# NodeMCU1_0.net
KiCad netlist of a schematic drawn in Altium Designer
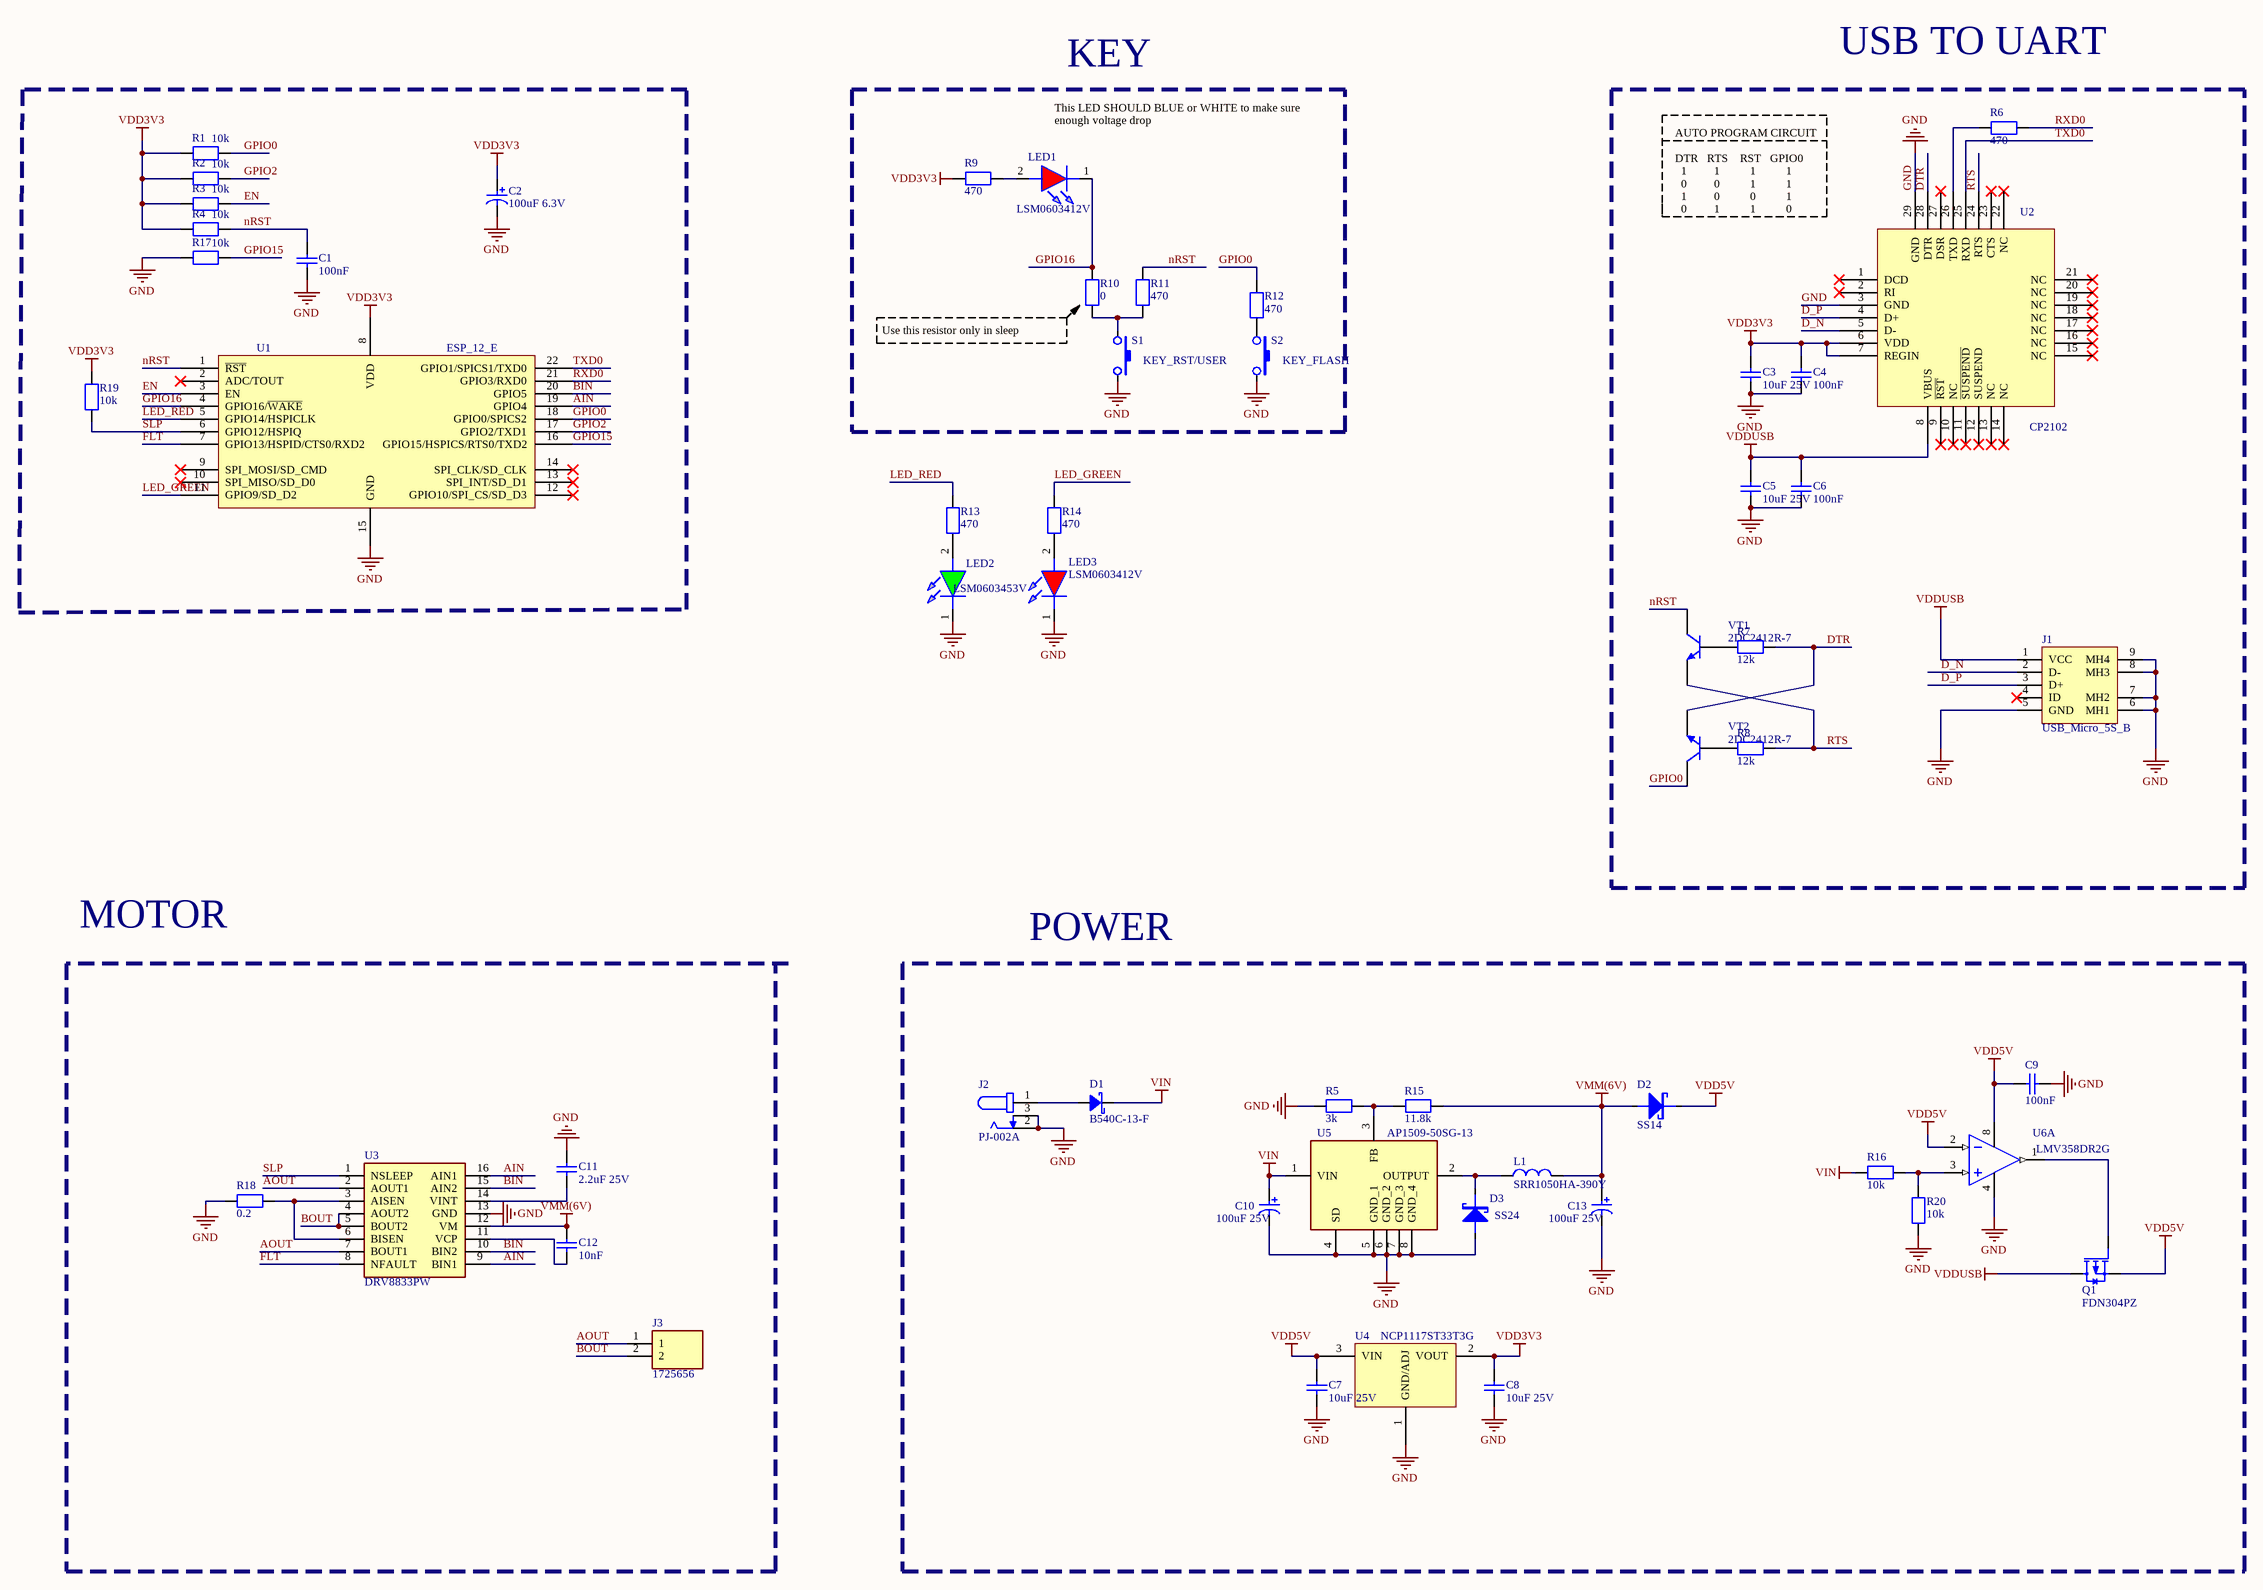
[diagram p0: NodeMCU1.0.SchDoc]

(export (version "E")
  (design (tool "Eeschema 10.0.6"))
  (components
    (comp (ref "C1")
      (value "100nF")
      (footprint "SMT_C_0603")
      (description "Multilayer Ceramic Capacitors MLCC - SMD/SMT 50V 100nF X7R 0603 10%")
      (fields
        (field (name "MANUFACTURER") "Yageo")
        (field (name "MANUFACTURER PART NUMBER") "CS0603KRX7R9BB104")
      )
      (libsource (lib "NodeMCU1.0") (part "SMT CAP 100nF 50V(0603)"))
    )
    (comp (ref "C2")
      (value "100uF 6.3V")
      (footprint "SMT_C_Tantalum_B")
      (description "Tantalum Capacitors - Solid SMD 6.3V 100uF 1210 ESR=1.7Ohms 20%")
      (fields
        (field (name "MANUFACTURER PART NUMBER") "TAJB107M006RNJ")
        (field (name "MANUFACTURER") "KYOCERA AVX")
      )
      (libsource (lib "NodeMCU1.0") (part "SMT ECAP 100uF(SMT_C)"))
    )
    (comp (ref "C3")
      (value "10uF 25V")
      (footprint "SMT_C_0603")
      (description "Multilayer Ceramic Capacitors MLCC - SMD/SMT 25 V 10 uF X5R 0603 20%")
      (fields
        (field (name "MANUFACTURER PART NUMBER") "CC0603MRX5R8BB106")
        (field (name "MANUFACTURER") "YAGEO")
      )
      (libsource (lib "NodeMCU1.0") (part "SMT CAP 10uF 25V(0603)"))
    )
    (comp (ref "C4")
      (value "100nF")
      (footprint "SMT_C_0603")
      (description "Multilayer Ceramic Capacitors MLCC - SMD/SMT 50V 100nF X7R 0603 10%")
      (fields
        (field (name "MANUFACTURER") "Yageo")
        (field (name "MANUFACTURER PART NUMBER") "CS0603KRX7R9BB104")
      )
      (libsource (lib "NodeMCU1.0") (part "SMT CAP 100nF 50V(0603)"))
    )
    (comp (ref "C5")
      (value "10uF 25V")
      (footprint "SMT_C_0603")
      (description "Multilayer Ceramic Capacitors MLCC - SMD/SMT 25 V 10 uF X5R 0603 20%")
      (fields
        (field (name "MANUFACTURER PART NUMBER") "CC0603MRX5R8BB106")
        (field (name "MANUFACTURER") "YAGEO")
      )
      (libsource (lib "NodeMCU1.0") (part "SMT CAP 10uF 25V(0603)"))
    )
    (comp (ref "C6")
      (value "100nF")
      (footprint "SMT_C_0603")
      (description "Multilayer Ceramic Capacitors MLCC - SMD/SMT 50V 100nF X7R 0603 10%")
      (fields
        (field (name "MANUFACTURER") "Yageo")
        (field (name "MANUFACTURER PART NUMBER") "CS0603KRX7R9BB104")
      )
      (libsource (lib "NodeMCU1.0") (part "SMT CAP 100nF 50V(0603)"))
    )
    (comp (ref "C7")
      (value "10uF 25V")
      (footprint "SMT_C_0805")
      (description "Multilayer Ceramic Capacitors MLCC - SMD/SMT 25 V 10 uF X6S 0805 10%")
      (fields
        (field (name "MANUFACTURER PART NUMBER") "CC0805KKX6S8BB106")
        (field (name "MANUFACTURER") "YAGEO")
      )
      (libsource (lib "NodeMCU1.0") (part "SMT CAP 10uF 25V(0805)"))
    )
    (comp (ref "C8")
      (value "10uF 25V")
      (footprint "SMT_C_0603")
      (description "Multilayer Ceramic Capacitors MLCC - SMD/SMT 25 V 10 uF X5R 0603 20%")
      (fields
        (field (name "MANUFACTURER PART NUMBER") "CC0603MRX5R8BB106")
        (field (name "MANUFACTURER") "YAGEO")
      )
      (libsource (lib "NodeMCU1.0") (part "SMT CAP 10uF 25V(0603)"))
    )
    (comp (ref "C9")
      (value "100nF")
      (footprint "SMT_C_0603")
      (description "Multilayer Ceramic Capacitors MLCC - SMD/SMT 50V 100nF X7R 0603 10%")
      (fields
        (field (name "MANUFACTURER") "Yageo")
        (field (name "MANUFACTURER PART NUMBER") "CS0603KRX7R9BB104")
      )
      (libsource (lib "NodeMCU1.0") (part "SMT CAP 100nF 50V(0603)"))
    )
    (comp (ref "C10")
      (value "100uF 25V")
      (footprint "CAPPRD250W50D630H1250")
      (description "Aluminium Electrolytic Capacitors - Radial Leaded 25V 100uF 85C 2k Hour Radial")
      (fields
        (field (name "MANUFACTURER") "Kemet")
        (field (name "MANUFACTURER PART NUMBER") "ESK107M025AE3AA")
      )
      (libsource (lib "NodeMCU1.0") (part "ECAP 100uF 25V"))
    )
    (comp (ref "C11")
      (value "2.2uF 25V")
      (footprint "SMT_C_0603")
      (description "Multilayer Ceramic Capacitors MLCC - SMD/SMT 25 V 2.2 uF X5R 0603 20%")
      (fields
        (field (name "MANUFACTURER PART NUMBER") "CC0603MRX5R8BB225")
        (field (name "MANUFACTURER") "YAGEO")
      )
      (libsource (lib "NodeMCU1.0") (part "SMT CAP 2.2uF 25V(0603)"))
    )
    (comp (ref "C12")
      (value "10nF")
      (footprint "SMT_C_0603")
      (description "Multilayer Ceramic Capacitors MLCC - SMD/SMT 50V 10nF X7R 0603 10%")
      (fields
        (field (name "MANUFACTURER") "Yageo")
        (field (name "MANUFACTURER PART NUMBER") "CS0603KRX7R9BB103")
      )
      (libsource (lib "NodeMCU1.0") (part "SMT CAP 10nF 50V(0603)"))
    )
    (comp (ref "C13")
      (value "100uF 25V")
      (footprint "CAPPRD250W50D630H1250")
      (description "Aluminium Electrolytic Capacitors - Radial Leaded 25V 100uF 85C 2k Hour Radial")
      (fields
        (field (name "MANUFACTURER") "Kemet")
        (field (name "MANUFACTURER PART NUMBER") "ESK107M025AE3AA")
      )
      (libsource (lib "NodeMCU1.0") (part "ECAP 100uF 25V"))
    )
    (comp (ref "D1")
      (value "B540C-13-F")
      (footprint "B540C-13-F")
      (description "DIODE SCHOTTKY 40V 5A SMC")
      (fields (field (name "MANUFACTURER") "Diodes"))
      (libsource (lib "NodeMCU1.0") (part "DIODE 10TQ035"))
    )
    (comp (ref "D2")
      (value "SS14")
      (footprint "SS14")
      (description "Schottky Diodes & Rectifiers SMA 40V 1.0A")
      (fields (field (name "MANUFACTURER") "onsemi / Fairchild"))
      (libsource (lib "NodeMCU1.0") (part "SS14"))
    )
    (comp (ref "D3")
      (value "SS24")
      (footprint "DIOM5436X247N")
      (description "Schottky Diodes & Rectifiers 2A, 40V, Schottky Rectifier")
      (fields (field (name "MANUFACTURER") "Taiwan Semiconductor"))
      (libsource (lib "NodeMCU1.0") (part "SS24"))
    )
    (comp (ref "J1")
      (value "USB_Micro_5S_B")
      (footprint "USB_MICRO_5S_B")
      (description "USB micro female SMT with 4 fixed foot")
      (fields
        (field (name "MANUFACTURER PART NUMBER") "614105150721")
        (field (name "MANUFACTURER") "Wurth Electronics")
      )
      (libsource (lib "NodeMCU1.0") (part "USB_Micro_5S_B"))
    )
    (comp (ref "J2")
      (value "PJ-002A")
      (footprint "PJ002A")
      (description "CONN PWR JACK 2X5.5MM SOLDER")
      (fields (field (name "MANUFACTURER") "CUI Devices"))
      (libsource (lib "NodeMCU1.0") (part "PJ-002A"))
    )
    (comp (ref "J3")
      (value "1725656")
      (footprint "1725656")
      (fields (field (name "MANUFACTURER") "Phoenix Contact"))
      (libsource (lib "NodeMCU1.0") (part "1725656"))
    )
    (comp (ref "L1")
      (value "SRR1050HA-390Y")
      (footprint "INDPM102100X510N")
      (description "Ind,10x10.2x4.8mm,39uH+/-30%,2.25A,shd")
      (fields (field (name "MANUFACTURER") "Bourns"))
      (libsource (lib "NodeMCU1.0") (part "INDUCTOR 39uH 2.25A"))
    )
    (comp (ref "LED1")
      (value "LSM0603412V")
      (footprint "LSM0603412V")
      (description "Standard LEDs - SMD SMD 0603 2V 100mcd RED")
      (fields (field (name "MANUFACTURER") "Visual Communications Company"))
      (libsource (lib "NodeMCU1.0") (part "LSM0603412V"))
    )
    (comp (ref "LED2")
      (value "LSM0603453V")
      (footprint "LEDC1608X55N")
      (description "Standard LEDs - SMD SMD 0603 3V 1000mcd GREEN")
      (fields (field (name "MANUFACTURER") "Visual Communications Company"))
      (libsource (lib "NodeMCU1.0") (part "LSM0603453V"))
    )
    (comp (ref "LED3")
      (value "LSM0603412V")
      (footprint "LSM0603412V")
      (description "Standard LEDs - SMD SMD 0603 2V 100mcd RED")
      (fields (field (name "MANUFACTURER") "Visual Communications Company"))
      (libsource (lib "NodeMCU1.0") (part "LSM0603412V"))
    )
    (comp (ref "Q1")
      (value "FDN304PZ")
      (footprint "SOT95P251X112-3N")
      (description "P-Channel MOSFET")
      (fields (field (name "MANUFACTURER") "onsemi / Fairchild"))
      (libsource (lib "NodeMCU1.0") (part "MOSFET-P"))
    )
    (comp (ref "R1")
      (value "10k")
      (footprint "SMT_R_0603")
      (description "Thick Film Resistors - SMD 10 kOhms 100mW 0603 1%")
      (fields
        (field (name "MANUFACTURER") "Yageo")
        (field (name "MANUFACTURER PART NUMBER") "RC0603FR-0710KL")
      )
      (libsource (lib "NodeMCU1.0") (part "RES 10K 0.1W 1%"))
    )
    (comp (ref "R2")
      (value "10k")
      (footprint "SMT_R_0603")
      (description "Thick Film Resistors - SMD 10 kOhms 100mW 0603 1%")
      (fields
        (field (name "MANUFACTURER") "Yageo")
        (field (name "MANUFACTURER PART NUMBER") "RC0603FR-0710KL")
      )
      (libsource (lib "NodeMCU1.0") (part "RES 10K 0.1W 1%"))
    )
    (comp (ref "R3")
      (value "10k")
      (footprint "SMT_R_0603")
      (description "Thick Film Resistors - SMD 10 kOhms 100mW 0603 1%")
      (fields
        (field (name "MANUFACTURER") "Yageo")
        (field (name "MANUFACTURER PART NUMBER") "RC0603FR-0710KL")
      )
      (libsource (lib "NodeMCU1.0") (part "RES 10K 0.1W 1%"))
    )
    (comp (ref "R4")
      (value "10k")
      (footprint "SMT_R_0603")
      (description "Thick Film Resistors - SMD 10 kOhms 100mW 0603 1%")
      (fields
        (field (name "MANUFACTURER") "Yageo")
        (field (name "MANUFACTURER PART NUMBER") "RC0603FR-0710KL")
      )
      (libsource (lib "NodeMCU1.0") (part "RES 10K 0.1W 1%"))
    )
    (comp (ref "R5")
      (value "3k")
      (footprint "SMT_R_0603")
      (description "Thick Film Resistors - SMD 3 kOhms 100mW 0603 1%")
      (fields
        (field (name "MANUFACTURER") "Yageo")
        (field (name "MANUFACTURER PART NUMBER") "RC0603FR-073KL")
      )
      (libsource (lib "NodeMCU1.0") (part "RES 3K 0.1W 1%"))
    )
    (comp (ref "R6")
      (value "470")
      (footprint "SMT_R_0603")
      (description "Thick Film Resistors - SMD 470 Ohms 100mW 0603 1%")
      (fields
        (field (name "MANUFACTURER") "Yageo")
        (field (name "MANUFACTURER PART NUMBER") "RC0603FR-07470RL")
      )
      (libsource (lib "NodeMCU1.0") (part "RES 470 0.1W 1%"))
    )
    (comp (ref "R7")
      (value "12k")
      (footprint "SMT_R_0603")
      (description "Thick Film Resistors - SMD 12 kOhms 100mW 0603 1%")
      (fields
        (field (name "MANUFACTURER") "Yageo")
        (field (name "MANUFACTURER PART NUMBER") "RC0603FR-0712KL")
      )
      (libsource (lib "NodeMCU1.0") (part "RES 12K 0.1W 1%"))
    )
    (comp (ref "R8")
      (value "12k")
      (footprint "SMT_R_0603")
      (description "Thick Film Resistors - SMD 12 kOhms 100mW 0603 1%")
      (fields
        (field (name "MANUFACTURER") "Yageo")
        (field (name "MANUFACTURER PART NUMBER") "RC0603FR-0712KL")
      )
      (libsource (lib "NodeMCU1.0") (part "RES 12K 0.1W 1%"))
    )
    (comp (ref "R9")
      (value "470")
      (footprint "SMT_R_0603")
      (description "Thick Film Resistors - SMD 470 Ohms 100mW 0603 1%")
      (fields
        (field (name "MANUFACTURER") "Yageo")
        (field (name "MANUFACTURER PART NUMBER") "RC0603FR-07470RL")
      )
      (libsource (lib "NodeMCU1.0") (part "RES 470 0.1W 1%"))
    )
    (comp (ref "R10")
      (value "0")
      (footprint "SMT_R_0603")
      (description "Thick Film Resistors - SMD 0 Ohms 100mW 0603 1%")
      (fields
        (field (name "MANUFACTURER") "Yageo")
        (field (name "MANUFACTURER PART NUMBER") "RC0603FR-070RL")
      )
      (libsource (lib "NodeMCU1.0") (part "RES 0 0.1W 1%"))
    )
    (comp (ref "R11")
      (value "470")
      (footprint "SMT_R_0603")
      (description "Thick Film Resistors - SMD 470 Ohms 100mW 0603 1%")
      (fields
        (field (name "MANUFACTURER") "Yageo")
        (field (name "MANUFACTURER PART NUMBER") "RC0603FR-07470RL")
      )
      (libsource (lib "NodeMCU1.0") (part "RES 470 0.1W 1%"))
    )
    (comp (ref "R12")
      (value "470")
      (footprint "SMT_R_0603")
      (description "Thick Film Resistors - SMD 470 Ohms 100mW 0603 1%")
      (fields
        (field (name "MANUFACTURER") "Yageo")
        (field (name "MANUFACTURER PART NUMBER") "RC0603FR-07470RL")
      )
      (libsource (lib "NodeMCU1.0") (part "RES 470 0.1W 1%"))
    )
    (comp (ref "R13")
      (value "470")
      (footprint "SMT_R_0603")
      (description "Thick Film Resistors - SMD 470 Ohms 100mW 0603 1%")
      (fields
        (field (name "MANUFACTURER") "Yageo")
        (field (name "MANUFACTURER PART NUMBER") "RC0603FR-07470RL")
      )
      (libsource (lib "NodeMCU1.0") (part "RES 470 0.1W 1%"))
    )
    (comp (ref "R14")
      (value "470")
      (footprint "SMT_R_0603")
      (description "Thick Film Resistors - SMD 470 Ohms 100mW 0603 1%")
      (fields
        (field (name "MANUFACTURER") "Yageo")
        (field (name "MANUFACTURER PART NUMBER") "RC0603FR-07470RL")
      )
      (libsource (lib "NodeMCU1.0") (part "RES 470 0.1W 1%"))
    )
    (comp (ref "R15")
      (value "11.8k")
      (footprint "SMT_R_0603")
      (description "Thick Film Resistors - SMD 11.8 kOhms 100mW 0603 1%")
      (fields
        (field (name "MANUFACTURER") "Yageo")
        (field (name "MANUFACTURER PART NUMBER") "RC0603FR-0711K8L")
      )
      (libsource (lib "NodeMCU1.0") (part "RES 11.8K 0.1W 1%"))
    )
    (comp (ref "R16")
      (value "10k")
      (footprint "SMT_R_0603")
      (description "Thick Film Resistors - SMD 10 kOhms 100mW 0603 1%")
      (fields
        (field (name "MANUFACTURER") "Yageo")
        (field (name "MANUFACTURER PART NUMBER") "RC0603FR-0710KL")
      )
      (libsource (lib "NodeMCU1.0") (part "RES 10K 0.1W 1%"))
    )
    (comp (ref "R17")
      (value "10k")
      (footprint "SMT_R_0603")
      (description "Thick Film Resistors - SMD 10 kOhms 100mW 0603 1%")
      (fields
        (field (name "MANUFACTURER") "Yageo")
        (field (name "MANUFACTURER PART NUMBER") "RC0603FR-0710KL")
      )
      (libsource (lib "NodeMCU1.0") (part "RES 10K 0.1W 1%"))
    )
    (comp (ref "R18")
      (value "0.2")
      (footprint "RESC5025X65N")
      (description "Current Sense Resistors 200 mOhms 750mW 5 % 600 ppm/C AEC-Q200")
      (fields
        (field (name "MANUFACTURER") "Yageo")
        (field (name "MANUFACTURER PART NUMBER") "RL2010JK-070R2L")
      )
      (libsource (lib "NodeMCU1.0") (part "RES 0.2 0.75W 5%"))
    )
    (comp (ref "R19")
      (value "10k")
      (footprint "SMT_R_0603")
      (description "Thick Film Resistors - SMD 10 kOhms 100mW 0603 1%")
      (fields
        (field (name "MANUFACTURER") "Yageo")
        (field (name "MANUFACTURER PART NUMBER") "RC0603FR-0710KL")
      )
      (libsource (lib "NodeMCU1.0") (part "RES 10K 0.1W 1%"))
    )
    (comp (ref "R20")
      (value "10k")
      (footprint "SMT_R_0603")
      (description "Thick Film Resistors - SMD 10 kOhms 100mW 0603 1%")
      (fields
        (field (name "MANUFACTURER") "Yageo")
        (field (name "MANUFACTURER PART NUMBER") "RC0603FR-0710KL")
      )
      (libsource (lib "NodeMCU1.0") (part "RES 10K 0.1W 1%"))
    )
    (comp (ref "S1")
      (value "KEY_RST/USER")
      (footprint "SMT_SW_PTS_820")
      (description "SMT Tactile ‎Switch PTS 820 Series")
      (fields
        (field (name "MANUFACTURER PART NUMBER") "PTS820J25MSMTRLFS")
        (field (name "MANUFACTURER") "C&K")
      )
      (libsource (lib "NodeMCU1.0") (part "SMT SW PTS_820"))
    )
    (comp (ref "S2")
      (value "KEY_FLASH")
      (footprint "SMT_SW_PTS_820")
      (description "SMT Tactile ‎Switch PTS 820 Series")
      (fields
        (field (name "MANUFACTURER PART NUMBER") "PTS820J25MSMTRLFS")
        (field (name "MANUFACTURER") "C&K")
      )
      (libsource (lib "NodeMCU1.0") (part "SMT SW PTS_820"))
    )
    (comp (ref "U1")
      (value "ESP_12_E")
      (footprint "ESP_12_E_L")
      (description "ESP-12 Wi-Fi Module by AI-Thinker")
      (fields (field (name "MANUFACTURER PART NUMBER") "ESP-12E") (field (name "MANUFACTURER") "china"))
      (libsource (lib "NodeMCU1.0") (part "ESP_12_E"))
    )
    (comp (ref "U2")
      (value "CP2102")
      (footprint "CP2102")
      (description "USB Interface IC USBXpress - USB to UART Bridge QFN28")
      (fields
        (field (name "MANUFACTURER PART NUMBER") "CP2102N-A02-GQFN28")
        (field (name "MANUFACTURER") "Silicon Labs")
      )
      (libsource (lib "NodeMCU1.0") (part "CP2102"))
    )
    (comp (ref "U3")
      (value "DRV8833PW")
      (footprint "DRV8833PW")
      (description "Motor / Motion / Ignition Controllers & Drivers DRV8833 EVAL MOD")
      (fields (field (name "MANUFACTURER") "Texas Instruments"))
      (libsource (lib "NodeMCU1.0") (part "DRV8833PW"))
    )
    (comp (ref "U4")
      (value "NCP1117ST33T3G")
      (footprint "SOT-223")
      (description "LDO Voltage Regulators 3.3V 1A Positive")
      (fields (field (name "MANUFACTURER") "onsemi"))
      (libsource (lib "NodeMCU1.0") (part "NCP1117"))
    )
    (comp (ref "U5")
      (value "AP1509-50SG-13")
      (footprint "SOIC127P600X175-8N")
      (description "DiodesZetex, AP1509-50SG-13 DC-DC Converter 2A 8-Pin, SOP")
      (fields (field (name "MANUFACTURER") "Diodes Inc."))
      (libsource (lib "NodeMCU1.0") (part "AP1509-50SG-13"))
    )
    (comp (ref "U6")
      (value "LMV358DR2G")
      (footprint "SOIC127P600X175-8N")
      (description "Operational Amplifiers - Op Amps LV R2R DUAL OP AMP")
      (fields (field (name "MANUFACTURER") "onsemi"))
      (libsource (lib "NodeMCU1.0") (part "LMV358DR2G"))
    )
    (comp (ref "VT1")
      (value "2DC2412R-7")
      (footprint "SMT_TRIODE_NPN")
      (description "Bipolar Transistors - BJT 50V NPN SMT")
      (fields (field (name "MANUFACTURER") "Diodes Incorporated"))
      (libsource (lib "NodeMCU1.0") (part "SMT_TRIODE_NPN"))
    )
    (comp (ref "VT2")
      (value "2DC2412R-7")
      (footprint "SMT_TRIODE_NPN")
      (description "Bipolar Transistors - BJT 50V NPN SMT")
      (fields (field (name "MANUFACTURER") "Diodes Incorporated"))
      (libsource (lib "NodeMCU1.0") (part "SMT_TRIODE_NPN"))
    )
  )
  (nets
    (net (code "1") (name "/AIN") (class "Default")
      (node (ref "U1") (pin "19") (pinfunction "GPIO4_19") (pintype "passive"))
      (node (ref "U3") (pin "16") (pinfunction "AIN1_16") (pintype "passive"))
      (node (ref "U3") (pin "9") (pinfunction "BIN1_9") (pintype "passive"))
    )
    (net (code "2") (name "/AOUT") (class "Default")
      (node (ref "J3") (pin "1") (pinfunction "1_1") (pintype "passive"))
      (node (ref "U3") (pin "2") (pinfunction "AOUT1_2") (pintype "passive"))
      (node (ref "U3") (pin "7") (pinfunction "BOUT1_7") (pintype "passive"))
    )
    (net (code "3") (name "/BIN") (class "Default")
      (node (ref "U1") (pin "20") (pinfunction "GPIO5_20") (pintype "passive"))
      (node (ref "U3") (pin "10") (pinfunction "BIN2_10") (pintype "passive"))
      (node (ref "U3") (pin "15") (pinfunction "AIN2_15") (pintype "passive"))
    )
    (net (code "4") (name "/BOUT") (class "Default")
      (node (ref "J3") (pin "2") (pinfunction "2_2") (pintype "passive"))
      (node (ref "U3") (pin "4") (pinfunction "AOUT2_4") (pintype "passive"))
      (node (ref "U3") (pin "5") (pinfunction "BOUT2_5") (pintype "passive"))
    )
    (net (code "5") (name "/DTR") (class "Default")
      (node (ref "R7") (pin "2") (pinfunction "2_2") (pintype "passive"))
      (node (ref "U2") (pin "28") (pinfunction "DTR_28") (pintype "passive"))
      (node (ref "VT2") (pin "2") (pinfunction "E_2") (pintype "passive"))
    )
    (net (code "6") (name "/D_N") (class "Default")
      (node (ref "J1") (pin "2") (pinfunction "D-_2") (pintype "passive"))
      (node (ref "U2") (pin "5") (pinfunction "D-_5") (pintype "passive"))
    )
    (net (code "7") (name "/D_P") (class "Default")
      (node (ref "J1") (pin "3") (pinfunction "D+_3") (pintype "passive"))
      (node (ref "U2") (pin "4") (pinfunction "D+_4") (pintype "passive"))
    )
    (net (code "8") (name "/EN") (class "Default")
      (node (ref "R3") (pin "2") (pinfunction "2_2") (pintype "passive"))
      (node (ref "U1") (pin "3") (pinfunction "EN_3") (pintype "passive"))
    )
    (net (code "9") (name "/FLT") (class "Default")
      (node (ref "U1") (pin "7") (pinfunction "GPIO13/HSPID/CTS0/RXD2_7") (pintype "passive"))
      (node (ref "U3") (pin "8") (pinfunction "NFAULT_8") (pintype "passive"))
    )
    (net (code "10") (name "/GPIO0") (class "Default")
      (node (ref "R1") (pin "2") (pinfunction "2_2") (pintype "passive"))
      (node (ref "R12") (pin "2") (pinfunction "2_2") (pintype "passive"))
      (node (ref "U1") (pin "18") (pinfunction "GPIO0/SPICS2_18") (pintype "passive"))
      (node (ref "VT2") (pin "3") (pinfunction "C_3") (pintype "passive"))
    )
    (net (code "11") (name "/GPIO2") (class "Default")
      (node (ref "R2") (pin "2") (pinfunction "2_2") (pintype "passive"))
      (node (ref "U1") (pin "17") (pinfunction "GPIO2/TXD1_17") (pintype "passive"))
    )
    (net (code "12") (name "/GPIO15") (class "Default")
      (node (ref "R17") (pin "2") (pinfunction "2_2") (pintype "passive"))
      (node (ref "U1") (pin "16") (pinfunction "GPIO15/HSPICS/RTS0/TXD2_16") (pintype "passive"))
    )
    (net (code "13") (name "/GPIO16") (class "Default")
      (node (ref "LED1") (pin "1") (pinfunction "K_1") (pintype "passive"))
      (node (ref "R10") (pin "2") (pinfunction "2_2") (pintype "passive"))
      (node (ref "U1") (pin "4") (pinfunction "GPIO16/~{WAKE}_4") (pintype "passive"))
    )
    (net (code "14") (name "/LED_GREEN") (class "Default")
      (node (ref "R14") (pin "1") (pinfunction "1_1") (pintype "passive"))
      (node (ref "U1") (pin "11") (pinfunction "GPIO9/SD_D2_11") (pintype "passive"))
    )
    (net (code "15") (name "/LED_RED") (class "Default")
      (node (ref "R13") (pin "1") (pinfunction "1_1") (pintype "passive"))
      (node (ref "U1") (pin "5") (pinfunction "GPIO14/HSPICLK_5") (pintype "passive"))
    )
    (net (code "16") (name "/RTS") (class "Default")
      (node (ref "R8") (pin "2") (pinfunction "2_2") (pintype "passive"))
      (node (ref "U2") (pin "24") (pinfunction "RTS_24") (pintype "passive"))
      (node (ref "VT1") (pin "2") (pinfunction "E_2") (pintype "passive"))
    )
    (net (code "17") (name "/RXD0") (class "Default")
      (node (ref "R6") (pin "2") (pinfunction "2_2") (pintype "passive"))
      (node (ref "U1") (pin "21") (pinfunction "GPIO3/RXD0_21") (pintype "passive"))
    )
    (net (code "18") (name "/SLP") (class "Default")
      (node (ref "R19") (pin "1") (pinfunction "1_1") (pintype "passive"))
      (node (ref "U1") (pin "6") (pinfunction "GPIO12/HSPIQ_6") (pintype "passive"))
      (node (ref "U3") (pin "1") (pinfunction "NSLEEP_1") (pintype "passive"))
    )
    (net (code "19") (name "/TXD0") (class "Default")
      (node (ref "U1") (pin "22") (pinfunction "GPIO1/SPICS1/TXD0_22") (pintype "passive"))
      (node (ref "U2") (pin "25") (pinfunction "RXD_25") (pintype "passive"))
    )
    (net (code "20") (name "/nRST") (class "Default")
      (node (ref "C1") (pin "2") (pinfunction "2_2") (pintype "passive"))
      (node (ref "R11") (pin "2") (pinfunction "2_2") (pintype "passive"))
      (node (ref "R4") (pin "2") (pinfunction "2_2") (pintype "passive"))
      (node (ref "U1") (pin "1") (pinfunction "~{RST}_1") (pintype "passive"))
      (node (ref "VT1") (pin "3") (pinfunction "C_3") (pintype "passive"))
    )
    (net (code "21") (name "GND") (class "Default")
      (node (ref "C1") (pin "1") (pinfunction "1_1") (pintype "passive"))
      (node (ref "C10") (pin "2") (pinfunction "2_2") (pintype "passive"))
      (node (ref "C11") (pin "1") (pinfunction "1_1") (pintype "passive"))
      (node (ref "C13") (pin "2") (pinfunction "2_2") (pintype "passive"))
      (node (ref "C2") (pin "2") (pinfunction "2_2") (pintype "passive"))
      (node (ref "C3") (pin "1") (pinfunction "1_1") (pintype "passive"))
      (node (ref "C4") (pin "1") (pinfunction "1_1") (pintype "passive"))
      (node (ref "C5") (pin "1") (pinfunction "1_1") (pintype "passive"))
      (node (ref "C6") (pin "1") (pinfunction "1_1") (pintype "passive"))
      (node (ref "C7") (pin "1") (pinfunction "1_1") (pintype "passive"))
      (node (ref "C8") (pin "1") (pinfunction "1_1") (pintype "passive"))
      (node (ref "C9") (pin "2") (pinfunction "2_2") (pintype "passive"))
      (node (ref "D3") (pin "2") (pinfunction "A_2") (pintype "passive"))
      (node (ref "J1") (pin "5") (pinfunction "GND_5") (pintype "passive"))
      (node (ref "J1") (pin "6") (pinfunction "MH1_6") (pintype "passive"))
      (node (ref "J1") (pin "7") (pinfunction "MH2_7") (pintype "passive"))
      (node (ref "J1") (pin "8") (pinfunction "MH3_8") (pintype "passive"))
      (node (ref "J1") (pin "9") (pinfunction "MH4_9") (pintype "passive"))
      (node (ref "J2") (pin "2") (pinfunction "2_2") (pintype "passive"))
      (node (ref "J2") (pin "3") (pinfunction "3_3") (pintype "passive"))
      (node (ref "LED2") (pin "1") (pinfunction "K_1") (pintype "passive"))
      (node (ref "LED3") (pin "1") (pinfunction "K_1") (pintype "passive"))
      (node (ref "R17") (pin "1") (pinfunction "1_1") (pintype "passive"))
      (node (ref "R18") (pin "1") (pinfunction "1_1") (pintype "passive"))
      (node (ref "R20") (pin "1") (pinfunction "1_1") (pintype "passive"))
      (node (ref "R5") (pin "1") (pinfunction "1_1") (pintype "passive"))
      (node (ref "S1") (pin "2") (pinfunction "2_2") (pintype "passive"))
      (node (ref "S2") (pin "2") (pinfunction "2_2") (pintype "passive"))
      (node (ref "U1") (pin "15") (pinfunction "GND_15") (pintype "passive"))
      (node (ref "U2") (pin "29") (pinfunction "GND_29") (pintype "passive"))
      (node (ref "U2") (pin "3") (pinfunction "GND_3") (pintype "passive"))
      (node (ref "U3") (pin "13") (pinfunction "GND_13") (pintype "passive"))
      (node (ref "U4") (pin "1") (pinfunction "GND/ADJ_1") (pintype "passive"))
      (node (ref "U5") (pin "4") (pinfunction "SD_4") (pintype "passive"))
      (node (ref "U5") (pin "5") (pinfunction "GND_1_5") (pintype "passive"))
      (node (ref "U5") (pin "6") (pinfunction "GND_2_6") (pintype "passive"))
      (node (ref "U5") (pin "7") (pinfunction "GND_3_7") (pintype "passive"))
      (node (ref "U5") (pin "8") (pinfunction "GND_4_8") (pintype "passive"))
      (node (ref "U6") (pin "4") (pinfunction "V-_4") (pintype "passive"))
    )
    (net (code "22") (name "Net-(D1-PadA)") (class "Default")
      (node (ref "D1") (pin "A") (pinfunction "A_A") (pintype "passive"))
      (node (ref "J2") (pin "1") (pinfunction "1_1") (pintype "passive"))
    )
    (net (code "23") (name "Net-(D3-K)") (class "Default")
      (node (ref "D3") (pin "1") (pinfunction "K_1") (pintype "passive"))
      (node (ref "L1") (pin "1") (pinfunction "1_1") (pintype "passive"))
      (node (ref "U5") (pin "2") (pinfunction "OUTPUT_2") (pintype "passive"))
    )
    (net (code "24") (name "Net-(LED1-A)") (class "Default")
      (node (ref "LED1") (pin "2") (pinfunction "A_2") (pintype "passive"))
      (node (ref "R9") (pin "1") (pinfunction "1_1") (pintype "passive"))
    )
    (net (code "25") (name "Net-(LED2-A)") (class "Default")
      (node (ref "LED2") (pin "2") (pinfunction "A_2") (pintype "passive"))
      (node (ref "R13") (pin "2") (pinfunction "2_2") (pintype "passive"))
    )
    (net (code "26") (name "Net-(LED3-A)") (class "Default")
      (node (ref "LED3") (pin "2") (pinfunction "A_2") (pintype "passive"))
      (node (ref "R14") (pin "2") (pinfunction "2_2") (pintype "passive"))
    )
    (net (code "27") (name "Net-(Q1-G)") (class "Default")
      (node (ref "Q1") (pin "1") (pinfunction "G_1") (pintype "passive"))
      (node (ref "U6") (pin "1") (pinfunction "OUT_A_1") (pintype "output"))
    )
    (net (code "28") (name "Net-(R10-Pad1)") (class "Default")
      (node (ref "R10") (pin "1") (pinfunction "1_1") (pintype "passive"))
      (node (ref "R11") (pin "1") (pinfunction "1_1") (pintype "passive"))
      (node (ref "S1") (pin "1") (pinfunction "1_1") (pintype "passive"))
    )
    (net (code "29") (name "Net-(R12-Pad1)") (class "Default")
      (node (ref "R12") (pin "1") (pinfunction "1_1") (pintype "passive"))
      (node (ref "S2") (pin "1") (pinfunction "1_1") (pintype "passive"))
    )
    (net (code "30") (name "Net-(U2-TXD)") (class "Default")
      (node (ref "R6") (pin "1") (pinfunction "1_1") (pintype "passive"))
      (node (ref "U2") (pin "26") (pinfunction "TXD_26") (pintype "passive"))
    )
    (net (code "31") (name "Net-(U3-AISEN)") (class "Default")
      (node (ref "R18") (pin "2") (pinfunction "2_2") (pintype "passive"))
      (node (ref "U3") (pin "3") (pinfunction "AISEN_3") (pintype "passive"))
      (node (ref "U3") (pin "6") (pinfunction "BISEN_6") (pintype "passive"))
    )
    (net (code "32") (name "Net-(U3-VCP)") (class "Default")
      (node (ref "C12") (pin "1") (pinfunction "1_1") (pintype "passive"))
      (node (ref "U3") (pin "11") (pinfunction "VCP_11") (pintype "passive"))
    )
    (net (code "33") (name "Net-(U3-VINT)") (class "Default")
      (node (ref "C11") (pin "2") (pinfunction "2_2") (pintype "passive"))
      (node (ref "U3") (pin "14") (pinfunction "VINT_14") (pintype "passive"))
    )
    (net (code "34") (name "Net-(U5-FB)") (class "Default")
      (node (ref "R15") (pin "1") (pinfunction "1_1") (pintype "passive"))
      (node (ref "R5") (pin "2") (pinfunction "2_2") (pintype "passive"))
      (node (ref "U5") (pin "3") (pinfunction "FB_3") (pintype "passive"))
    )
    (net (code "35") (name "Net-(U6A-IN_A+)") (class "Default")
      (node (ref "R16") (pin "1") (pinfunction "1_1") (pintype "passive"))
      (node (ref "R20") (pin "2") (pinfunction "2_2") (pintype "passive"))
      (node (ref "U6") (pin "3") (pinfunction "IN_A+_3") (pintype "input"))
    )
    (net (code "36") (name "Net-(VT1-B)") (class "Default")
      (node (ref "R7") (pin "1") (pinfunction "1_1") (pintype "passive"))
      (node (ref "VT1") (pin "1") (pinfunction "B_1") (pintype "passive"))
    )
    (net (code "37") (name "Net-(VT2-B)") (class "Default")
      (node (ref "R8") (pin "1") (pinfunction "1_1") (pintype "passive"))
      (node (ref "VT2") (pin "1") (pinfunction "B_1") (pintype "passive"))
    )
    (net (code "38") (name "VDD3V3") (class "Default")
      (node (ref "C2") (pin "1") (pinfunction "1_1") (pintype "passive"))
      (node (ref "C3") (pin "2") (pinfunction "2_2") (pintype "passive"))
      (node (ref "C4") (pin "2") (pinfunction "2_2") (pintype "passive"))
      (node (ref "C8") (pin "2") (pinfunction "2_2") (pintype "passive"))
      (node (ref "R1") (pin "1") (pinfunction "1_1") (pintype "passive"))
      (node (ref "R19") (pin "2") (pinfunction "2_2") (pintype "passive"))
      (node (ref "R2") (pin "1") (pinfunction "1_1") (pintype "passive"))
      (node (ref "R3") (pin "1") (pinfunction "1_1") (pintype "passive"))
      (node (ref "R4") (pin "1") (pinfunction "1_1") (pintype "passive"))
      (node (ref "R9") (pin "2") (pinfunction "2_2") (pintype "passive"))
      (node (ref "U1") (pin "8") (pinfunction "VDD_8") (pintype "passive"))
      (node (ref "U2") (pin "6") (pinfunction "VDD_6") (pintype "passive"))
      (node (ref "U2") (pin "7") (pinfunction "REGIN_7") (pintype "passive"))
      (node (ref "U4") (pin "2") (pinfunction "VOUT_2") (pintype "passive"))
    )
    (net (code "39") (name "VDD5V") (class "Default")
      (node (ref "C7") (pin "2") (pinfunction "2_2") (pintype "passive"))
      (node (ref "C9") (pin "1") (pinfunction "1_1") (pintype "passive"))
      (node (ref "D2") (pin "1") (pinfunction "K_1") (pintype "passive"))
      (node (ref "Q1") (pin "2") (pinfunction "S_2") (pintype "passive"))
      (node (ref "U4") (pin "3") (pinfunction "VIN_3") (pintype "passive"))
      (node (ref "U6") (pin "2") (pinfunction "IN_A-_2") (pintype "input"))
      (node (ref "U6") (pin "8") (pinfunction "V+_8") (pintype "passive"))
    )
    (net (code "40") (name "VDDUSB") (class "Default")
      (node (ref "C5") (pin "2") (pinfunction "2_2") (pintype "passive"))
      (node (ref "C6") (pin "2") (pinfunction "2_2") (pintype "passive"))
      (node (ref "J1") (pin "1") (pinfunction "VCC_1") (pintype "passive"))
      (node (ref "Q1") (pin "3") (pinfunction "D_3") (pintype "passive"))
      (node (ref "U2") (pin "8") (pinfunction "VBUS_8") (pintype "passive"))
    )
    (net (code "41") (name "VIN") (class "Default")
      (node (ref "C10") (pin "1") (pinfunction "1_1") (pintype "passive"))
      (node (ref "D1") (pin "K") (pinfunction "K_K") (pintype "passive"))
      (node (ref "R16") (pin "2") (pinfunction "2_2") (pintype "passive"))
      (node (ref "U5") (pin "1") (pinfunction "VIN_1") (pintype "passive"))
    )
    (net (code "42") (name "VMM(6V)") (class "Default")
      (node (ref "C12") (pin "2") (pinfunction "2_2") (pintype "passive"))
      (node (ref "C13") (pin "1") (pinfunction "1_1") (pintype "passive"))
      (node (ref "D2") (pin "2") (pinfunction "A_2") (pintype "passive"))
      (node (ref "L1") (pin "2") (pinfunction "2_2") (pintype "passive"))
      (node (ref "R15") (pin "2") (pinfunction "2_2") (pintype "passive"))
      (node (ref "U3") (pin "12") (pinfunction "VM_12") (pintype "passive"))
    )
    (net (code "43") (name "unconnected-(J1-ID-Pad4)") (class "Default")
      (node (ref "J1") (pin "4") (pinfunction "ID_4") (pintype "passive+no_connect"))
    )
    (net (code "44") (name "unconnected-(U1-ADC{slash}TOUT-Pad2)") (class "Default")
      (node (ref "U1") (pin "2") (pinfunction "ADC/TOUT_2") (pintype "passive+no_connect"))
    )
    (net (code "45") (name "unconnected-(U1-GPIO10{slash}SPI_CS{slash}SD_D3-Pad12)") (class "Default")
      (node (ref "U1") (pin "12") (pinfunction "GPIO10/SPI_CS/SD_D3_12") (pintype "passive+no_connect"))
    )
    (net (code "46") (name "unconnected-(U1-SPI_CLK{slash}SD_CLK-Pad14)") (class "Default")
      (node (ref "U1") (pin "14") (pinfunction "SPI_CLK/SD_CLK_14") (pintype "passive+no_connect"))
    )
    (net (code "47") (name "unconnected-(U1-SPI_INT{slash}SD_D1-Pad13)") (class "Default")
      (node (ref "U1") (pin "13") (pinfunction "SPI_INT/SD_D1_13") (pintype "passive+no_connect"))
    )
    (net (code "48") (name "unconnected-(U1-SPI_MISO{slash}SD_D0-Pad10)") (class "Default")
      (node (ref "U1") (pin "10") (pinfunction "SPI_MISO/SD_D0_10") (pintype "passive+no_connect"))
    )
    (net (code "49") (name "unconnected-(U1-SPI_MOSI{slash}SD_CMD-Pad9)") (class "Default")
      (node (ref "U1") (pin "9") (pinfunction "SPI_MOSI/SD_CMD_9") (pintype "passive+no_connect"))
    )
    (net (code "50") (name "unconnected-(U2-CTS-Pad23)") (class "Default")
      (node (ref "U2") (pin "23") (pinfunction "CTS_23") (pintype "passive+no_connect"))
    )
    (net (code "51") (name "unconnected-(U2-DCD-Pad1)") (class "Default")
      (node (ref "U2") (pin "1") (pinfunction "DCD_1") (pintype "passive+no_connect"))
    )
    (net (code "52") (name "unconnected-(U2-DSR-Pad27)") (class "Default")
      (node (ref "U2") (pin "27") (pinfunction "DSR_27") (pintype "passive+no_connect"))
    )
    (net (code "53") (name "unconnected-(U2-NC-Pad10)") (class "Default")
      (node (ref "U2") (pin "10") (pinfunction "NC_10") (pintype "passive+no_connect"))
    )
    (net (code "54") (name "unconnected-(U2-NC-Pad13)") (class "Default")
      (node (ref "U2") (pin "13") (pinfunction "NC_13") (pintype "passive+no_connect"))
    )
    (net (code "55") (name "unconnected-(U2-NC-Pad14)") (class "Default")
      (node (ref "U2") (pin "14") (pinfunction "NC_14") (pintype "passive+no_connect"))
    )
    (net (code "56") (name "unconnected-(U2-NC-Pad15)") (class "Default")
      (node (ref "U2") (pin "15") (pinfunction "NC_15") (pintype "passive+no_connect"))
    )
    (net (code "57") (name "unconnected-(U2-NC-Pad16)") (class "Default")
      (node (ref "U2") (pin "16") (pinfunction "NC_16") (pintype "passive+no_connect"))
    )
    (net (code "58") (name "unconnected-(U2-NC-Pad17)") (class "Default")
      (node (ref "U2") (pin "17") (pinfunction "NC_17") (pintype "passive+no_connect"))
    )
    (net (code "59") (name "unconnected-(U2-NC-Pad18)") (class "Default")
      (node (ref "U2") (pin "18") (pinfunction "NC_18") (pintype "passive+no_connect"))
    )
    (net (code "60") (name "unconnected-(U2-NC-Pad19)") (class "Default")
      (node (ref "U2") (pin "19") (pinfunction "NC_19") (pintype "passive+no_connect"))
    )
    (net (code "61") (name "unconnected-(U2-NC-Pad20)") (class "Default")
      (node (ref "U2") (pin "20") (pinfunction "NC_20") (pintype "passive+no_connect"))
    )
    (net (code "62") (name "unconnected-(U2-NC-Pad21)") (class "Default")
      (node (ref "U2") (pin "21") (pinfunction "NC_21") (pintype "passive+no_connect"))
    )
    (net (code "63") (name "unconnected-(U2-NC-Pad22)") (class "Default")
      (node (ref "U2") (pin "22") (pinfunction "NC_22") (pintype "passive+no_connect"))
    )
    (net (code "64") (name "unconnected-(U2-RI-Pad2)") (class "Default")
      (node (ref "U2") (pin "2") (pinfunction "RI_2") (pintype "passive+no_connect"))
    )
    (net (code "65") (name "unconnected-(U2-SUSPEND-Pad12)") (class "Default")
      (node (ref "U2") (pin "12") (pinfunction "SUSPEND_12") (pintype "passive+no_connect"))
    )
    (net (code "66") (name "unconnected-(U2-~{RST}-Pad9)") (class "Default")
      (node (ref "U2") (pin "9") (pinfunction "~{RST}_9") (pintype "passive+no_connect"))
    )
    (net (code "67") (name "unconnected-(U2-~{SUSPEND}-Pad11)") (class "Default")
      (node (ref "U2") (pin "11") (pinfunction "~{SUSPEND}_11") (pintype "passive+no_connect"))
    )
  )
)
